# random-keypad-door-controller-v01.net
KiCad netlist of a schematic drawn in EAGLE
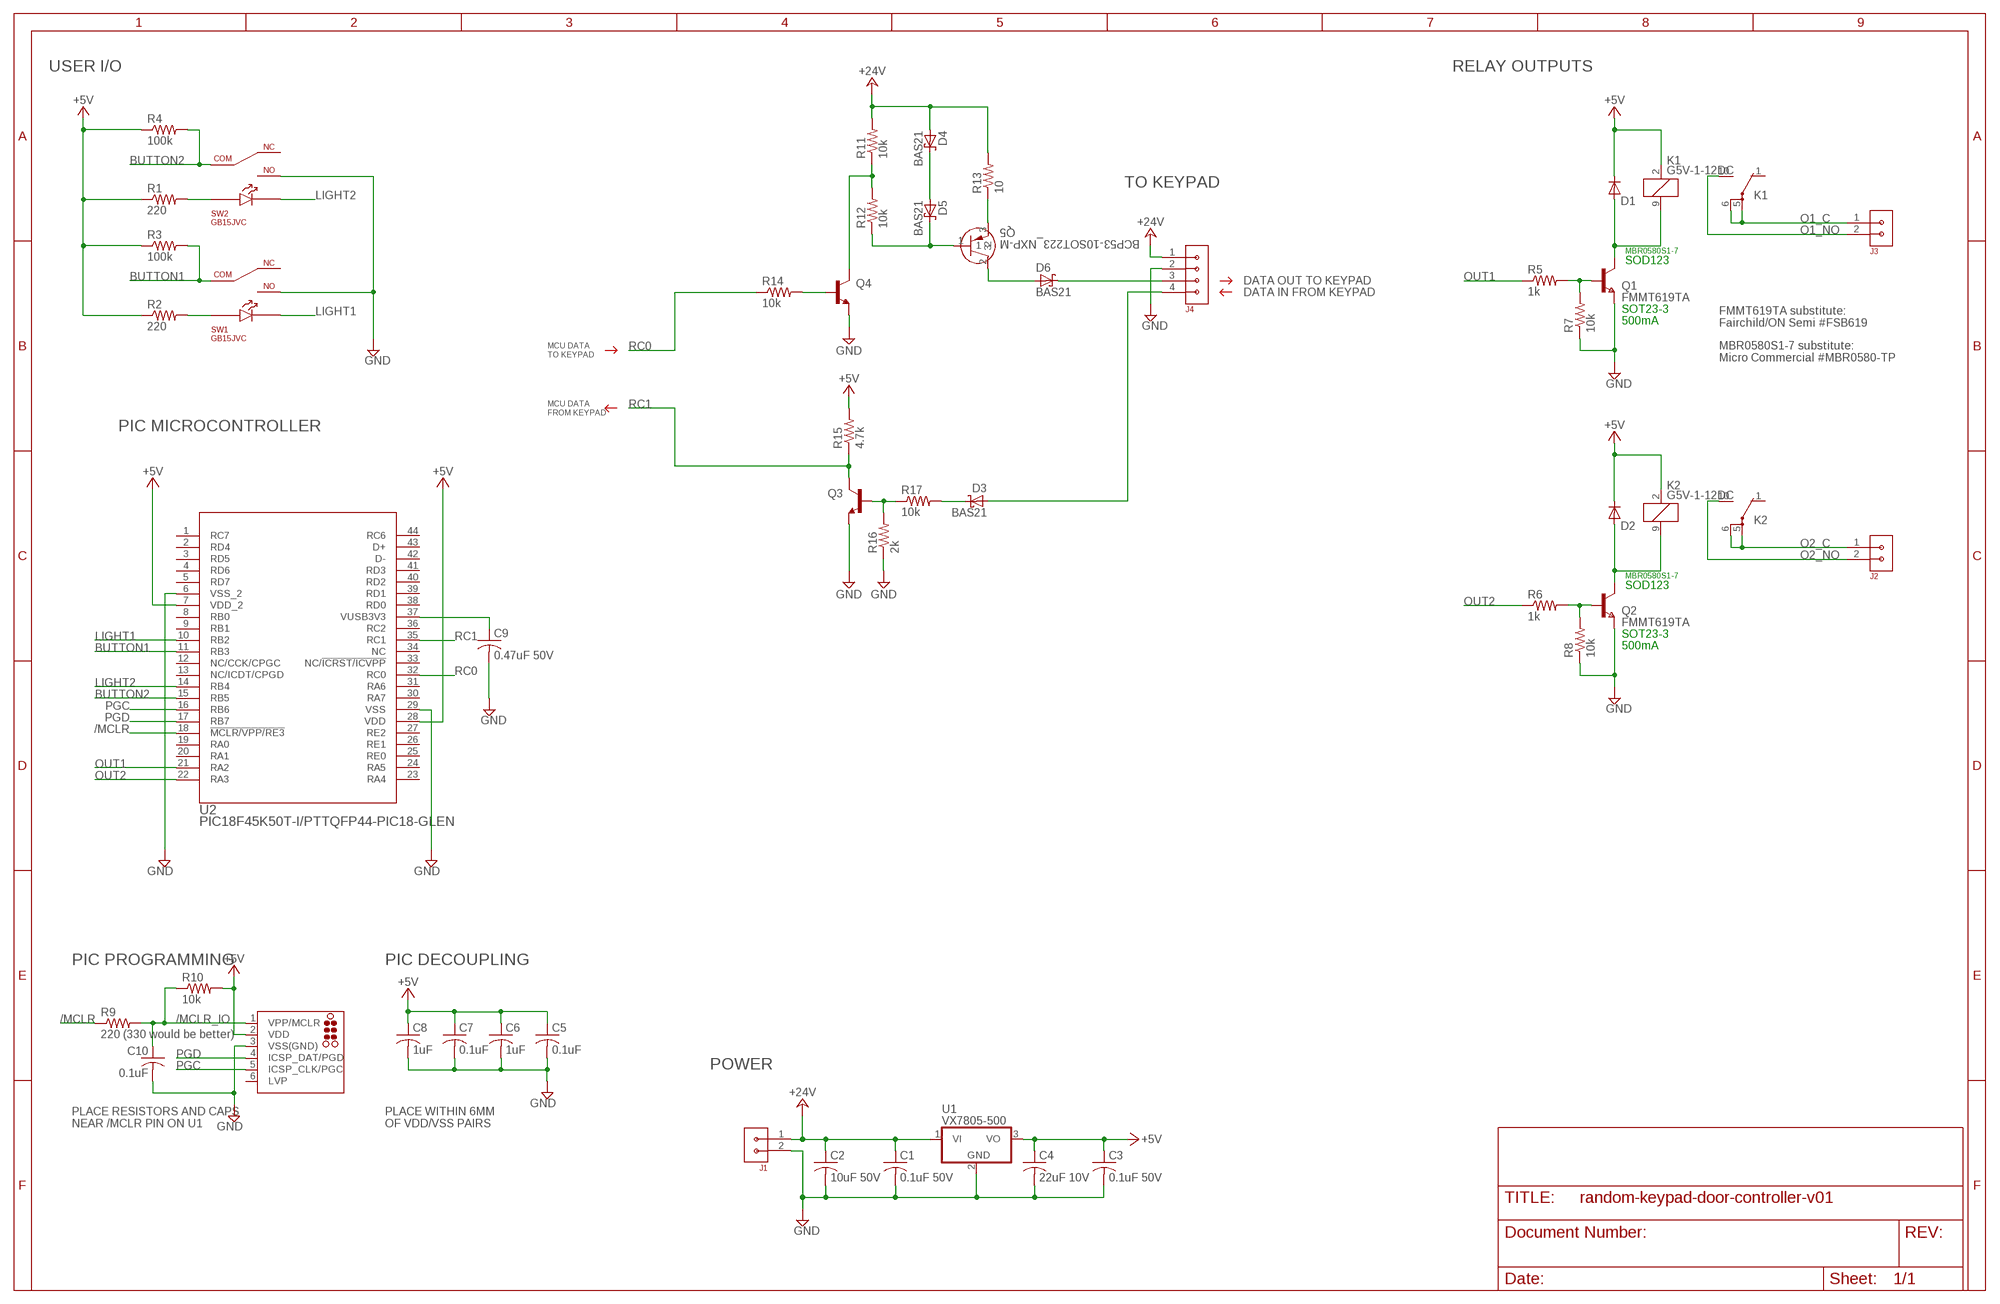
[diagram p0: schematic, sheet 1]

(export (version "E")
  (design (tool "Eeschema 10.0.6"))
  (components
    (comp (ref "C1")
      (value "0.1uF 50V")
      (footprint "eagle-import:C1206K")
      (fields (field (name "MFR") "KEMET") (field (name "MFR_PART_NO") "C1206S104M5RACTU"))
      (libsource (lib "eagle-import") (part "C-USC1206K"))
    )
    (comp (ref "C2")
      (value "10uF 50V")
      (footprint "eagle-import:C1210K")
      (fields (field (name "MFR") "KEMET") (field (name "MFR_PART_NO") "C1210C106K5RACTU"))
      (libsource (lib "eagle-import") (part "C-USC1210K"))
    )
    (comp (ref "C3")
      (value "0.1uF 50V")
      (footprint "eagle-import:C1206K")
      (fields (field (name "MFR") "KEMET") (field (name "MFR_PART_NO") "C1206S104M5RACTU"))
      (libsource (lib "eagle-import") (part "C-USC1206K"))
    )
    (comp (ref "C4")
      (value "22uF 10V")
      (footprint "eagle-import:C1206K")
      (fields (field (name "MFR") "KEMET") (field (name "MFR_PART_NO") "C1206C226K8RAC7800"))
      (libsource (lib "eagle-import") (part "C-USC1206K"))
    )
    (comp (ref "C5")
      (value "0.1uF")
      (footprint "eagle-import:C0603K")
      (libsource (lib "eagle-import") (part "C-USC0603K"))
    )
    (comp (ref "C6")
      (value "1uF")
      (footprint "eagle-import:C0603K")
      (libsource (lib "eagle-import") (part "C-USC0603K"))
    )
    (comp (ref "C7")
      (value "0.1uF")
      (footprint "eagle-import:C0603K")
      (libsource (lib "eagle-import") (part "C-USC0603K"))
    )
    (comp (ref "C8")
      (value "1uF")
      (footprint "eagle-import:C0603K")
      (libsource (lib "eagle-import") (part "C-USC0603K"))
    )
    (comp (ref "C9")
      (value "0.47uF 50V")
      (footprint "eagle-import:C1206K")
      (fields (field (name "MFR") "KEMET") (field (name "MFR_PART_NO") "C1206C474K5RACTU"))
      (libsource (lib "eagle-import") (part "C-USC1206K"))
    )
    (comp (ref "C10")
      (value "0.1uF")
      (footprint "eagle-import:C0603K")
      (libsource (lib "eagle-import") (part "C-USC0603K"))
    )
    (comp (ref "D1")
      (value "1N4148W-TP")
      (footprint "eagle-import:SOD123")
      (fields (field (name "MFR") "DIODES INC") (field (name "MFR_PART_NO") "MBR0580S1-7"))
      (libsource (lib "eagle-import") (part "DIODE-SOD123"))
    )
    (comp (ref "D2")
      (value "1N4148W-TP")
      (footprint "eagle-import:SOD123")
      (fields (field (name "MFR") "DIODES INC") (field (name "MFR_PART_NO") "MBR0580S1-7"))
      (libsource (lib "eagle-import") (part "DIODE-SOD123"))
    )
    (comp (ref "D3")
      (value "BAS21")
      (footprint "eagle-import:SOT23")
      (libsource (lib "eagle-import") (part "BAS40"))
    )
    (comp (ref "D4")
      (value "BAS21")
      (footprint "eagle-import:SOT23")
      (libsource (lib "eagle-import") (part "BAS40"))
    )
    (comp (ref "D5")
      (value "BAS21")
      (footprint "eagle-import:SOT23")
      (libsource (lib "eagle-import") (part "BAS40"))
    )
    (comp (ref "D6")
      (value "BAS21")
      (footprint "eagle-import:SOT23")
      (libsource (lib "eagle-import") (part "BAS40"))
    )
    (comp (ref "DEBUG")
      (value "TC2030-MCP-NL")
      (footprint "eagle-import:TC2030-MCP-NL")
      (libsource (lib "eagle-import") (part "TC2030-MCP-NL"))
    )
    (comp (ref "J1")
      (value "CON-3.81MM-1X2-PHOENIX")
      (footprint "eagle-import:CON-PHOENIX-3.81-1X2-RA")
      (libsource (lib "eagle-import") (part "CON-3.81MM-1X2-PHOENIX"))
    )
    (comp (ref "J2")
      (value "CON-3.81MM-1X2-PHOENIX")
      (footprint "eagle-import:CON-PHOENIX-3.81-1X2-RA")
      (libsource (lib "eagle-import") (part "CON-3.81MM-1X2-PHOENIX"))
    )
    (comp (ref "J3")
      (value "CON-3.81MM-1X2-PHOENIX")
      (footprint "eagle-import:CON-PHOENIX-3.81-1X2-RA")
      (libsource (lib "eagle-import") (part "CON-3.81MM-1X2-PHOENIX"))
    )
    (comp (ref "J4")
      (value "CON-3.81MM-1X4-PHOENIX-1803293")
      (footprint "eagle-import:CON-PHOENIX-1803293-3.81-1X4")
      (libsource (lib "eagle-import") (part "CON-3.81MM-1X4-PHOENIX-1803293"))
    )
    (comp (ref "K1")
      (value "G5V-1-12DC")
      (footprint "eagle-import:G5V1")
      (fields
        (field (name "MPN") "G5V-1-DC24")
        (field (name "MFR") "OMRON")
        (field (name "MFR_PART_NO") "G5V-1-DC5")
      )
      (libsource (lib "eagle-import") (part "G5V1"))
    )
    (comp (ref "K2")
      (value "G5V-1-12DC")
      (footprint "eagle-import:G5V1")
      (fields
        (field (name "MPN") "G5V-1-DC24")
        (field (name "MFR") "OMRON")
        (field (name "MFR_PART_NO") "G5V-1-DC5")
      )
      (libsource (lib "eagle-import") (part "G5V1"))
    )
    (comp (ref "Q1")
      (value "FMMT619TA")
      (footprint "eagle-import:SOT-23")
      (fields (field (name "MPN") "DSS20201L-7") (field (name "MFR") "DIODES INC"))
      (libsource (lib "eagle-import") (part "NPNSOT23"))
    )
    (comp (ref "Q2")
      (value "FMMT619TA")
      (footprint "eagle-import:SOT-23")
      (fields (field (name "MPN") "DSS20201L-7") (field (name "MFR") "DIODES INC"))
      (libsource (lib "eagle-import") (part "NPNSOT23"))
    )
    (comp (ref "Q3")
      (value "BC817-40-NPN-SOT23-BEC")
      (footprint "eagle-import:SOT23-BEC")
      (libsource (lib "eagle-import") (part "-NPN-SOT23-BECBC817-40"))
    )
    (comp (ref "Q4")
      (value "BC817-40-NPN-SOT23-BEC")
      (footprint "eagle-import:SOT23-BEC")
      (libsource (lib "eagle-import") (part "-NPN-SOT23-BECBC817-40"))
    )
    (comp (ref "Q5")
      (value "BCP53-10SOT223_NXP-M")
      (footprint "eagle-import:SOT223_NXP-M")
      (fields
        (field (name "MANUFACTURER_PART_NUMBER") "BCP53-10")
        (field (name "COPYRIGHT") "Copyright (C) 2021 Ultra Librarian. All rights reserved.")
      )
      (libsource (lib "eagle-import") (part "BCP53-10SOT223_NXP-M"))
    )
    (comp (ref "R1")
      (value "220")
      (footprint "eagle-import:R0603")
      (libsource (lib "eagle-import") (part "R-US_R0603"))
    )
    (comp (ref "R2")
      (value "220")
      (footprint "eagle-import:R0603")
      (libsource (lib "eagle-import") (part "R-US_R0603"))
    )
    (comp (ref "R3")
      (value "100k")
      (footprint "eagle-import:R0603")
      (libsource (lib "eagle-import") (part "R-US_R0603"))
    )
    (comp (ref "R4")
      (value "100k")
      (footprint "eagle-import:R0603")
      (libsource (lib "eagle-import") (part "R-US_R0603"))
    )
    (comp (ref "R5")
      (value "1k")
      (footprint "eagle-import:R0603")
      (fields (field (name "MFR") "BOURNS") (field (name "MFR_PART_NO") "CR1206-JW-102ELF"))
      (libsource (lib "eagle-import") (part "R-US_R0603"))
    )
    (comp (ref "R6")
      (value "1k")
      (footprint "eagle-import:R0603")
      (fields (field (name "MFR") "BOURNS") (field (name "MFR_PART_NO") "CR1206-JW-102ELF"))
      (libsource (lib "eagle-import") (part "R-US_R0603"))
    )
    (comp (ref "R7")
      (value "10k")
      (footprint "eagle-import:R0603")
      (fields (field (name "MFR") "BOURNS") (field (name "MFR_PART_NO") "CR1206-JW-102ELF"))
      (libsource (lib "eagle-import") (part "R-US_R0603"))
    )
    (comp (ref "R8")
      (value "10k")
      (footprint "eagle-import:R0603")
      (fields (field (name "MFR") "BOURNS") (field (name "MFR_PART_NO") "CR1206-JW-102ELF"))
      (libsource (lib "eagle-import") (part "R-US_R0603"))
    )
    (comp (ref "R9")
      (value "220 (330 would be better)")
      (footprint "eagle-import:R0603")
      (libsource (lib "eagle-import") (part "R-US_R0603"))
    )
    (comp (ref "R10")
      (value "10k")
      (footprint "eagle-import:R0603")
      (libsource (lib "eagle-import") (part "R-US_R0603"))
    )
    (comp (ref "R11")
      (value "10k")
      (footprint "eagle-import:R0603")
      (libsource (lib "eagle-import") (part "resistor_R-US_R0603"))
    )
    (comp (ref "R12")
      (value "10k")
      (footprint "eagle-import:R0603")
      (libsource (lib "eagle-import") (part "resistor_R-US_R0603"))
    )
    (comp (ref "R13")
      (value "10")
      (footprint "eagle-import:R0603")
      (libsource (lib "eagle-import") (part "resistor_R-US_R0603"))
    )
    (comp (ref "R14")
      (value "10k")
      (footprint "eagle-import:R0603")
      (libsource (lib "eagle-import") (part "resistor_R-US_R0603"))
    )
    (comp (ref "R15")
      (value "4.7k")
      (footprint "eagle-import:R0603")
      (libsource (lib "eagle-import") (part "resistor_R-US_R0603"))
    )
    (comp (ref "R16")
      (value "2k")
      (footprint "eagle-import:R0603")
      (libsource (lib "eagle-import") (part "resistor_R-US_R0603"))
    )
    (comp (ref "R17")
      (value "10k")
      (footprint "eagle-import:R0603")
      (libsource (lib "eagle-import") (part "resistor_R-US_R0603"))
    )
    (comp (ref "SW1")
      (value "GB15JVC")
      (footprint "eagle-import:GB15JHC")
      (libsource (lib "eagle-import") (part "GB15JHC"))
    )
    (comp (ref "SW2")
      (value "GB15JVC")
      (footprint "eagle-import:GB15JHC")
      (libsource (lib "eagle-import") (part "GB15JHC"))
    )
    (comp (ref "U1")
      (value "VX7805-500")
      (footprint "eagle-import:CUI-78XX-500")
      (libsource (lib "eagle-import") (part "CUI-V7803-500"))
    )
    (comp (ref "U2")
      (value "PIC18F45K50T-I/PTTQFP44-PIC18-GLEN")
      (footprint "eagle-import:TQFP44-PIC18-GLEN")
      (libsource (lib "eagle-import") (part "PIC18F45K50T-I/PTTQFP44-PIC18-GLEN"))
    )
  )
  (nets
    (net (code "1") (name "+5V") (class "Default")
      (node (ref "C3") (pin "1") (pinfunction "1_1") (pintype "passive"))
      (node (ref "C4") (pin "1") (pinfunction "1_1") (pintype "passive"))
      (node (ref "C5") (pin "1") (pinfunction "1_1") (pintype "passive"))
      (node (ref "C6") (pin "1") (pinfunction "1_1") (pintype "passive"))
      (node (ref "C7") (pin "1") (pinfunction "1_1") (pintype "passive"))
      (node (ref "C8") (pin "1") (pinfunction "1_1") (pintype "passive"))
      (node (ref "D1") (pin "C") (pinfunction "C_C") (pintype "passive"))
      (node (ref "D2") (pin "C") (pinfunction "C_C") (pintype "passive"))
      (node (ref "DEBUG") (pin "2") (pinfunction "VDD_2") (pintype "power_in"))
      (node (ref "K1") (pin "2") (pinfunction "1_2") (pintype "passive"))
      (node (ref "K2") (pin "2") (pinfunction "1_2") (pintype "passive"))
      (node (ref "R1") (pin "1") (pinfunction "1_1") (pintype "passive"))
      (node (ref "R10") (pin "2") (pinfunction "2_2") (pintype "passive"))
      (node (ref "R15") (pin "2") (pinfunction "2_2") (pintype "passive"))
      (node (ref "R2") (pin "1") (pinfunction "1_1") (pintype "passive"))
      (node (ref "R3") (pin "1") (pinfunction "1_1") (pintype "passive"))
      (node (ref "R4") (pin "1") (pinfunction "1_1") (pintype "passive"))
      (node (ref "U1") (pin "3") (pinfunction "VO_3") (pintype "passive"))
      (node (ref "U2") (pin "28") (pinfunction "VDD_28") (pintype "power_in"))
      (node (ref "U2") (pin "7") (pinfunction "VDD_2_7") (pintype "power_in"))
    )
    (net (code "2") (name "+24V") (class "Default")
      (node (ref "C1") (pin "1") (pinfunction "1_1") (pintype "passive"))
      (node (ref "C2") (pin "1") (pinfunction "1_1") (pintype "passive"))
      (node (ref "D4") (pin "1") (pinfunction "A_1") (pintype "passive"))
      (node (ref "J1") (pin "1") (pinfunction "1_1") (pintype "bidirectional"))
      (node (ref "J4") (pin "1") (pinfunction "1_1") (pintype "bidirectional"))
      (node (ref "R11") (pin "2") (pinfunction "2_2") (pintype "passive"))
      (node (ref "R13") (pin "2") (pinfunction "2_2") (pintype "passive"))
      (node (ref "U1") (pin "1") (pinfunction "VI_1") (pintype "input"))
    )
    (net (code "3") (name "/BUTTON1") (class "Default")
      (node (ref "R3") (pin "2") (pinfunction "2_2") (pintype "passive"))
      (node (ref "SW1") (pin "5") (pinfunction "5_5") (pintype "bidirectional"))
      (node (ref "U2") (pin "11") (pinfunction "RB3_11") (pintype "bidirectional"))
    )
    (net (code "4") (name "/BUTTON2") (class "Default")
      (node (ref "R4") (pin "2") (pinfunction "2_2") (pintype "passive"))
      (node (ref "SW2") (pin "5") (pinfunction "5_5") (pintype "bidirectional"))
      (node (ref "U2") (pin "15") (pinfunction "RB5_15") (pintype "bidirectional"))
    )
    (net (code "5") (name "/LIGHT1") (class "Default")
      (node (ref "SW1") (pin "3") (pinfunction "3_3") (pintype "bidirectional"))
      (node (ref "U2") (pin "10") (pinfunction "RB2_10") (pintype "bidirectional"))
    )
    (net (code "6") (name "/LIGHT2") (class "Default")
      (node (ref "SW2") (pin "3") (pinfunction "3_3") (pintype "bidirectional"))
      (node (ref "U2") (pin "14") (pinfunction "RB4_14") (pintype "bidirectional"))
    )
    (net (code "7") (name "/O1_C") (class "Default")
      (node (ref "J3") (pin "1") (pinfunction "1_1") (pintype "bidirectional"))
      (node (ref "K1") (pin "5") (pinfunction "P_5") (pintype "passive"))
      (node (ref "K1") (pin "6") (pinfunction "P_6") (pintype "passive"))
    )
    (net (code "8") (name "/O1_NO") (class "Default")
      (node (ref "J3") (pin "2") (pinfunction "2_2") (pintype "bidirectional"))
      (node (ref "K1") (pin "10") (pinfunction "S_10") (pintype "passive"))
    )
    (net (code "9") (name "/O2_C") (class "Default")
      (node (ref "J2") (pin "1") (pinfunction "1_1") (pintype "bidirectional"))
      (node (ref "K2") (pin "5") (pinfunction "P_5") (pintype "passive"))
      (node (ref "K2") (pin "6") (pinfunction "P_6") (pintype "passive"))
    )
    (net (code "10") (name "/O2_NO") (class "Default")
      (node (ref "J2") (pin "2") (pinfunction "2_2") (pintype "bidirectional"))
      (node (ref "K2") (pin "10") (pinfunction "S_10") (pintype "passive"))
    )
    (net (code "11") (name "/OUT1") (class "Default")
      (node (ref "R5") (pin "1") (pinfunction "1_1") (pintype "passive"))
      (node (ref "U2") (pin "21") (pinfunction "RA2_21") (pintype "bidirectional"))
    )
    (net (code "12") (name "/OUT2") (class "Default")
      (node (ref "R6") (pin "1") (pinfunction "1_1") (pintype "passive"))
      (node (ref "U2") (pin "22") (pinfunction "RA3_22") (pintype "bidirectional"))
    )
    (net (code "13") (name "/PGC") (class "Default")
      (node (ref "DEBUG") (pin "5") (pinfunction "ICSP_CLK/PGC_5") (pintype "output"))
      (node (ref "U2") (pin "16") (pinfunction "RB6_16") (pintype "bidirectional"))
    )
    (net (code "14") (name "/PGD") (class "Default")
      (node (ref "DEBUG") (pin "4") (pinfunction "ICSP_DAT/PGD_4") (pintype "bidirectional"))
      (node (ref "U2") (pin "17") (pinfunction "RB7_17") (pintype "bidirectional"))
    )
    (net (code "15") (name "/RC0") (class "Default")
      (node (ref "R14") (pin "1") (pinfunction "1_1") (pintype "passive"))
      (node (ref "U2") (pin "32") (pinfunction "RC0_32") (pintype "bidirectional"))
    )
    (net (code "16") (name "/RC1") (class "Default")
      (node (ref "Q3") (pin "C") (pinfunction "C_C") (pintype "passive"))
      (node (ref "R15") (pin "1") (pinfunction "1_1") (pintype "passive"))
      (node (ref "U2") (pin "35") (pinfunction "RC1_35") (pintype "bidirectional"))
    )
    (net (code "17") (name "/{slash}MCLR") (class "Default")
      (node (ref "R9") (pin "1") (pinfunction "1_1") (pintype "passive"))
      (node (ref "U2") (pin "18") (pinfunction "~{MCLR/VPP/RE3}_18") (pintype "bidirectional"))
    )
    (net (code "18") (name "/{slash}MCLR_IO") (class "Default")
      (node (ref "C10") (pin "1") (pinfunction "1_1") (pintype "passive"))
      (node (ref "DEBUG") (pin "1") (pinfunction "VPP/MCLR_1") (pintype "passive"))
      (node (ref "R10") (pin "1") (pinfunction "1_1") (pintype "passive"))
      (node (ref "R9") (pin "2") (pinfunction "2_2") (pintype "passive"))
    )
    (net (code "19") (name "GND") (class "Default")
      (node (ref "C1") (pin "2") (pinfunction "2_2") (pintype "passive"))
      (node (ref "C10") (pin "2") (pinfunction "2_2") (pintype "passive"))
      (node (ref "C2") (pin "2") (pinfunction "2_2") (pintype "passive"))
      (node (ref "C3") (pin "2") (pinfunction "2_2") (pintype "passive"))
      (node (ref "C4") (pin "2") (pinfunction "2_2") (pintype "passive"))
      (node (ref "C5") (pin "2") (pinfunction "2_2") (pintype "passive"))
      (node (ref "C6") (pin "2") (pinfunction "2_2") (pintype "passive"))
      (node (ref "C7") (pin "2") (pinfunction "2_2") (pintype "passive"))
      (node (ref "C8") (pin "2") (pinfunction "2_2") (pintype "passive"))
      (node (ref "C9") (pin "2") (pinfunction "2_2") (pintype "passive"))
      (node (ref "DEBUG") (pin "3") (pinfunction "VSS(GND)_3") (pintype "power_in"))
      (node (ref "J1") (pin "2") (pinfunction "2_2") (pintype "bidirectional"))
      (node (ref "J4") (pin "2") (pinfunction "2_2") (pintype "bidirectional"))
      (node (ref "Q1") (pin "2") (pinfunction "E_2") (pintype "passive"))
      (node (ref "Q2") (pin "2") (pinfunction "E_2") (pintype "passive"))
      (node (ref "Q3") (pin "E") (pinfunction "E_E") (pintype "passive"))
      (node (ref "Q4") (pin "E") (pinfunction "E_E") (pintype "passive"))
      (node (ref "R16") (pin "1") (pinfunction "1_1") (pintype "passive"))
      (node (ref "R7") (pin "1") (pinfunction "1_1") (pintype "passive"))
      (node (ref "R8") (pin "1") (pinfunction "1_1") (pintype "passive"))
      (node (ref "SW1") (pin "4") (pinfunction "4_4") (pintype "bidirectional"))
      (node (ref "SW2") (pin "4") (pinfunction "4_4") (pintype "bidirectional"))
      (node (ref "U1") (pin "2") (pinfunction "GND_2") (pintype "passive"))
      (node (ref "U2") (pin "29") (pinfunction "VSS_29") (pintype "power_in"))
      (node (ref "U2") (pin "6") (pinfunction "VSS_2_6") (pintype "power_in"))
    )
    (net (code "20") (name "Net-(D3-A)") (class "Default")
      (node (ref "D3") (pin "1") (pinfunction "A_1") (pintype "passive"))
      (node (ref "J4") (pin "4") (pinfunction "4_4") (pintype "bidirectional"))
    )
    (net (code "21") (name "Net-(D3-C)") (class "Default")
      (node (ref "D3") (pin "3") (pinfunction "C_3") (pintype "passive"))
      (node (ref "R17") (pin "2") (pinfunction "2_2") (pintype "passive"))
    )
    (net (code "22") (name "Net-(D4-C)") (class "Default")
      (node (ref "D4") (pin "3") (pinfunction "C_3") (pintype "passive"))
      (node (ref "D5") (pin "1") (pinfunction "A_1") (pintype "passive"))
    )
    (net (code "23") (name "Net-(D5-C)") (class "Default")
      (node (ref "D5") (pin "3") (pinfunction "C_3") (pintype "passive"))
      (node (ref "Q5") (pin "1") (pinfunction "1_1") (pintype "passive"))
      (node (ref "R12") (pin "1") (pinfunction "1_1") (pintype "passive"))
    )
    (net (code "24") (name "Net-(D6-A)") (class "Default")
      (node (ref "D6") (pin "1") (pinfunction "A_1") (pintype "passive"))
      (node (ref "Q5") (pin "2") (pinfunction "2_2") (pintype "passive"))
    )
    (net (code "25") (name "Net-(D6-C)") (class "Default")
      (node (ref "D6") (pin "3") (pinfunction "C_3") (pintype "passive"))
      (node (ref "J4") (pin "3") (pinfunction "3_3") (pintype "bidirectional"))
    )
    (net (code "26") (name "Net-(K1A-2)") (class "Default")
      (node (ref "D1") (pin "A") (pinfunction "A_A") (pintype "passive"))
      (node (ref "K1") (pin "9") (pinfunction "2_9") (pintype "passive"))
      (node (ref "Q1") (pin "1") (pinfunction "C_1") (pintype "passive"))
    )
    (net (code "27") (name "Net-(K2A-2)") (class "Default")
      (node (ref "D2") (pin "A") (pinfunction "A_A") (pintype "passive"))
      (node (ref "K2") (pin "9") (pinfunction "2_9") (pintype "passive"))
      (node (ref "Q2") (pin "1") (pinfunction "C_1") (pintype "passive"))
    )
    (net (code "28") (name "Net-(Q1-B)") (class "Default")
      (node (ref "Q1") (pin "3") (pinfunction "B_3") (pintype "passive"))
      (node (ref "R5") (pin "2") (pinfunction "2_2") (pintype "passive"))
      (node (ref "R7") (pin "2") (pinfunction "2_2") (pintype "passive"))
    )
    (net (code "29") (name "Net-(Q2-B)") (class "Default")
      (node (ref "Q2") (pin "3") (pinfunction "B_3") (pintype "passive"))
      (node (ref "R6") (pin "2") (pinfunction "2_2") (pintype "passive"))
      (node (ref "R8") (pin "2") (pinfunction "2_2") (pintype "passive"))
    )
    (net (code "30") (name "Net-(Q3-PadB)") (class "Default")
      (node (ref "Q3") (pin "B") (pinfunction "B_B") (pintype "passive"))
      (node (ref "R16") (pin "2") (pinfunction "2_2") (pintype "passive"))
      (node (ref "R17") (pin "1") (pinfunction "1_1") (pintype "passive"))
    )
    (net (code "31") (name "Net-(Q4-PadB)") (class "Default")
      (node (ref "Q4") (pin "B") (pinfunction "B_B") (pintype "passive"))
      (node (ref "R14") (pin "2") (pinfunction "2_2") (pintype "passive"))
    )
    (net (code "32") (name "Net-(Q4-PadC)") (class "Default")
      (node (ref "Q4") (pin "C") (pinfunction "C_C") (pintype "passive"))
      (node (ref "R11") (pin "1") (pinfunction "1_1") (pintype "passive"))
      (node (ref "R12") (pin "2") (pinfunction "2_2") (pintype "passive"))
    )
    (net (code "33") (name "Net-(Q5-Pad3)") (class "Default")
      (node (ref "Q5") (pin "3") (pinfunction "3_3") (pintype "passive"))
      (node (ref "R13") (pin "1") (pinfunction "1_1") (pintype "passive"))
    )
    (net (code "34") (name "Net-(R1-Pad2)") (class "Default")
      (node (ref "R1") (pin "2") (pinfunction "2_2") (pintype "passive"))
      (node (ref "SW2") (pin "1") (pinfunction "1_1") (pintype "bidirectional"))
    )
    (net (code "35") (name "Net-(R2-Pad2)") (class "Default")
      (node (ref "R2") (pin "2") (pinfunction "2_2") (pintype "passive"))
      (node (ref "SW1") (pin "1") (pinfunction "1_1") (pintype "bidirectional"))
    )
    (net (code "36") (name "Net-(U2-VUSB3V3)") (class "Default")
      (node (ref "C9") (pin "1") (pinfunction "1_1") (pintype "passive"))
      (node (ref "U2") (pin "37") (pinfunction "VUSB3V3_37") (pintype "power_in"))
    )
    (net (code "37") (name "unconnected-(DEBUG-LVP-Pad6)") (class "Default")
      (node (ref "DEBUG") (pin "6") (pinfunction "LVP_6") (pintype "bidirectional"))
    )
    (net (code "38") (name "unconnected-(K1B-O-Pad1)") (class "Default")
      (node (ref "K1") (pin "1") (pinfunction "O_1") (pintype "passive"))
    )
    (net (code "39") (name "unconnected-(K2B-O-Pad1)") (class "Default")
      (node (ref "K2") (pin "1") (pinfunction "O_1") (pintype "passive"))
    )
    (net (code "40") (name "unconnected-(SW1-Pad6)") (class "Default")
      (node (ref "SW1") (pin "6") (pinfunction "6_6") (pintype "bidirectional"))
    )
    (net (code "41") (name "unconnected-(SW2-Pad6)") (class "Default")
      (node (ref "SW2") (pin "6") (pinfunction "6_6") (pintype "bidirectional"))
    )
    (net (code "42") (name "unconnected-(U2-D+-Pad43)") (class "Default")
      (node (ref "U2") (pin "43") (pinfunction "D+_43") (pintype "passive"))
    )
    (net (code "43") (name "unconnected-(U2-D--Pad42)") (class "Default")
      (node (ref "U2") (pin "42") (pinfunction "D-_42") (pintype "passive"))
    )
    (net (code "44") (name "unconnected-(U2-NC-Pad34)") (class "Default")
      (node (ref "U2") (pin "34") (pinfunction "NC_34") (pintype "no_connect"))
    )
    (net (code "45") (name "unconnected-(U2-NC{slash}CCK{slash}CPGC-Pad12)") (class "Default")
      (node (ref "U2") (pin "12") (pinfunction "NC/CCK/CPGC_12") (pintype "bidirectional"))
    )
    (net (code "46") (name "unconnected-(U2-NC{slash}ICDT{slash}CPGD-Pad13)") (class "Default")
      (node (ref "U2") (pin "13") (pinfunction "NC/ICDT/CPGD_13") (pintype "bidirectional"))
    )
    (net (code "47") (name "unconnected-(U2-NC{slash}~{ICRST{slash}ICVPP}-Pad33)") (class "Default")
      (node (ref "U2") (pin "33") (pinfunction "NC/~{ICRST/ICVPP}_33") (pintype "bidirectional"))
    )
    (net (code "48") (name "unconnected-(U2-RA0-Pad19)") (class "Default")
      (node (ref "U2") (pin "19") (pinfunction "RA0_19") (pintype "bidirectional"))
    )
    (net (code "49") (name "unconnected-(U2-RA1-Pad20)") (class "Default")
      (node (ref "U2") (pin "20") (pinfunction "RA1_20") (pintype "bidirectional"))
    )
    (net (code "50") (name "unconnected-(U2-RA4-Pad23)") (class "Default")
      (node (ref "U2") (pin "23") (pinfunction "RA4_23") (pintype "bidirectional"))
    )
    (net (code "51") (name "unconnected-(U2-RA5-Pad24)") (class "Default")
      (node (ref "U2") (pin "24") (pinfunction "RA5_24") (pintype "bidirectional"))
    )
    (net (code "52") (name "unconnected-(U2-RA6-Pad31)") (class "Default")
      (node (ref "U2") (pin "31") (pinfunction "RA6_31") (pintype "bidirectional"))
    )
    (net (code "53") (name "unconnected-(U2-RA7-Pad30)") (class "Default")
      (node (ref "U2") (pin "30") (pinfunction "RA7_30") (pintype "bidirectional"))
    )
    (net (code "54") (name "unconnected-(U2-RB0-Pad8)") (class "Default")
      (node (ref "U2") (pin "8") (pinfunction "RB0_8") (pintype "bidirectional"))
    )
    (net (code "55") (name "unconnected-(U2-RB1-Pad9)") (class "Default")
      (node (ref "U2") (pin "9") (pinfunction "RB1_9") (pintype "bidirectional"))
    )
    (net (code "56") (name "unconnected-(U2-RC2-Pad36)") (class "Default")
      (node (ref "U2") (pin "36") (pinfunction "RC2_36") (pintype "bidirectional"))
    )
    (net (code "57") (name "unconnected-(U2-RC6-Pad44)") (class "Default")
      (node (ref "U2") (pin "44") (pinfunction "RC6_44") (pintype "bidirectional"))
    )
    (net (code "58") (name "unconnected-(U2-RC7-Pad1)") (class "Default")
      (node (ref "U2") (pin "1") (pinfunction "RC7_1") (pintype "bidirectional"))
    )
    (net (code "59") (name "unconnected-(U2-RD0-Pad38)") (class "Default")
      (node (ref "U2") (pin "38") (pinfunction "RD0_38") (pintype "bidirectional"))
    )
    (net (code "60") (name "unconnected-(U2-RD1-Pad39)") (class "Default")
      (node (ref "U2") (pin "39") (pinfunction "RD1_39") (pintype "bidirectional"))
    )
    (net (code "61") (name "unconnected-(U2-RD2-Pad40)") (class "Default")
      (node (ref "U2") (pin "40") (pinfunction "RD2_40") (pintype "bidirectional"))
    )
    (net (code "62") (name "unconnected-(U2-RD3-Pad41)") (class "Default")
      (node (ref "U2") (pin "41") (pinfunction "RD3_41") (pintype "bidirectional"))
    )
    (net (code "63") (name "unconnected-(U2-RD4-Pad2)") (class "Default")
      (node (ref "U2") (pin "2") (pinfunction "RD4_2") (pintype "bidirectional"))
    )
    (net (code "64") (name "unconnected-(U2-RD5-Pad3)") (class "Default")
      (node (ref "U2") (pin "3") (pinfunction "RD5_3") (pintype "bidirectional"))
    )
    (net (code "65") (name "unconnected-(U2-RD6-Pad4)") (class "Default")
      (node (ref "U2") (pin "4") (pinfunction "RD6_4") (pintype "bidirectional"))
    )
    (net (code "66") (name "unconnected-(U2-RD7-Pad5)") (class "Default")
      (node (ref "U2") (pin "5") (pinfunction "RD7_5") (pintype "bidirectional"))
    )
    (net (code "67") (name "unconnected-(U2-RE0-Pad25)") (class "Default")
      (node (ref "U2") (pin "25") (pinfunction "RE0_25") (pintype "bidirectional"))
    )
    (net (code "68") (name "unconnected-(U2-RE1-Pad26)") (class "Default")
      (node (ref "U2") (pin "26") (pinfunction "RE1_26") (pintype "bidirectional"))
    )
    (net (code "69") (name "unconnected-(U2-RE2-Pad27)") (class "Default")
      (node (ref "U2") (pin "27") (pinfunction "RE2_27") (pintype "bidirectional"))
    )
  )
)
